# PCI_dos_Motores.net
KiCad netlist of a schematic drawn in EAGLE
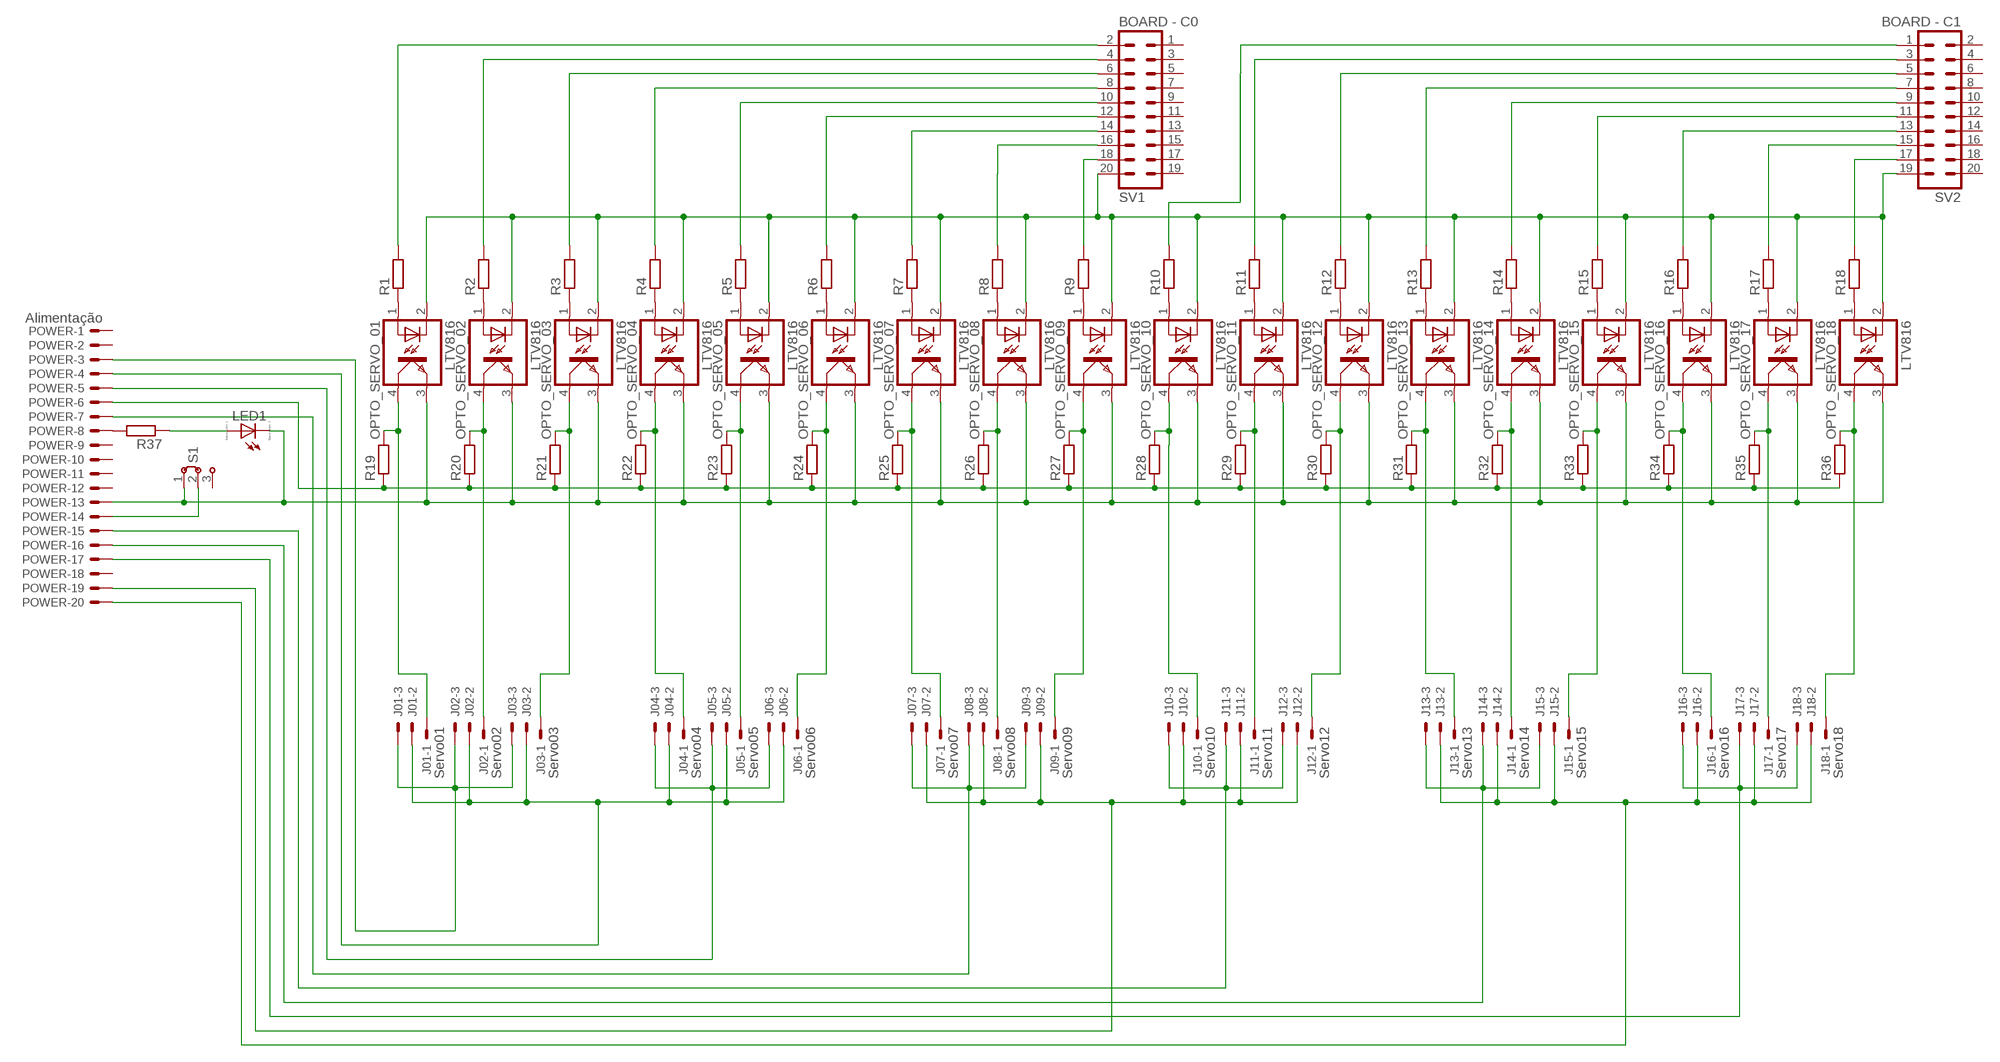
[diagram p0: schematic, sheet 1]

(export (version "E")
  (design (tool "Eeschema 10.0.6"))
  (components
    (comp (ref "J01")
      (value "Servo01")
      (footprint "eagle-import:7395-03")
      (libsource (lib "eagle-import") (part "22-?-0305-7038"))
    )
    (comp (ref "J02")
      (value "Servo02")
      (footprint "eagle-import:7395-03")
      (libsource (lib "eagle-import") (part "22-?-0305-7038"))
    )
    (comp (ref "J03")
      (value "Servo03")
      (footprint "eagle-import:7395-03")
      (libsource (lib "eagle-import") (part "22-?-0305-7038"))
    )
    (comp (ref "J04")
      (value "Servo04")
      (footprint "eagle-import:7395-03")
      (libsource (lib "eagle-import") (part "22-?-0305-7038"))
    )
    (comp (ref "J05")
      (value "Servo05")
      (footprint "eagle-import:7395-03")
      (libsource (lib "eagle-import") (part "22-?-0305-7038"))
    )
    (comp (ref "J06")
      (value "Servo06")
      (footprint "eagle-import:7395-03")
      (libsource (lib "eagle-import") (part "22-?-0305-7038"))
    )
    (comp (ref "J07")
      (value "Servo07")
      (footprint "eagle-import:7395-03")
      (libsource (lib "eagle-import") (part "22-?-0305-7038"))
    )
    (comp (ref "J08")
      (value "Servo08")
      (footprint "eagle-import:7395-03")
      (libsource (lib "eagle-import") (part "22-?-0305-7038"))
    )
    (comp (ref "J09")
      (value "Servo09")
      (footprint "eagle-import:7395-03")
      (libsource (lib "eagle-import") (part "22-?-0305-7038"))
    )
    (comp (ref "J10")
      (value "Servo10")
      (footprint "eagle-import:7395-03")
      (libsource (lib "eagle-import") (part "22-?-0305-7038"))
    )
    (comp (ref "J11")
      (value "Servo11")
      (footprint "eagle-import:7395-03")
      (libsource (lib "eagle-import") (part "22-?-0305-7038"))
    )
    (comp (ref "J12")
      (value "Servo12")
      (footprint "eagle-import:7395-03")
      (libsource (lib "eagle-import") (part "22-?-0305-7038"))
    )
    (comp (ref "J13")
      (value "Servo13")
      (footprint "eagle-import:7395-03")
      (libsource (lib "eagle-import") (part "22-?-0305-7038"))
    )
    (comp (ref "J14")
      (value "Servo14")
      (footprint "eagle-import:7395-03")
      (libsource (lib "eagle-import") (part "22-?-0305-7038"))
    )
    (comp (ref "J15")
      (value "Servo15")
      (footprint "eagle-import:7395-03")
      (libsource (lib "eagle-import") (part "22-?-0305-7038"))
    )
    (comp (ref "J16")
      (value "Servo16")
      (footprint "eagle-import:7395-03")
      (libsource (lib "eagle-import") (part "22-?-0305-7038"))
    )
    (comp (ref "J17")
      (value "Servo17")
      (footprint "eagle-import:7395-03")
      (libsource (lib "eagle-import") (part "22-?-0305-7038"))
    )
    (comp (ref "J18")
      (value "Servo18")
      (footprint "eagle-import:7395-03")
      (libsource (lib "eagle-import") (part "22-?-0305-7038"))
    )
    (comp (ref "LED1")
      (value "LED_ELD260")
      (footprint "eagle-import:LED_LD260")
      (libsource (lib "eagle-import") (part "LED_ELD260"))
    )
    (comp (ref "OPTO_SERVO_01")
      (value "LTV816")
      (footprint "eagle-import:DIL04")
      (libsource (lib "eagle-import") (part "LTV816"))
    )
    (comp (ref "OPTO_SERVO_02")
      (value "LTV816")
      (footprint "eagle-import:DIL04")
      (libsource (lib "eagle-import") (part "LTV816"))
    )
    (comp (ref "OPTO_SERVO_03")
      (value "LTV816")
      (footprint "eagle-import:DIL04")
      (libsource (lib "eagle-import") (part "LTV816"))
    )
    (comp (ref "OPTO_SERVO_04")
      (value "LTV816")
      (footprint "eagle-import:DIL04")
      (libsource (lib "eagle-import") (part "LTV816"))
    )
    (comp (ref "OPTO_SERVO_05")
      (value "LTV816")
      (footprint "eagle-import:DIL04")
      (libsource (lib "eagle-import") (part "LTV816"))
    )
    (comp (ref "OPTO_SERVO_06")
      (value "LTV816")
      (footprint "eagle-import:DIL04")
      (libsource (lib "eagle-import") (part "LTV816"))
    )
    (comp (ref "OPTO_SERVO_07")
      (value "LTV816")
      (footprint "eagle-import:DIL04")
      (libsource (lib "eagle-import") (part "LTV816"))
    )
    (comp (ref "OPTO_SERVO_08")
      (value "LTV816")
      (footprint "eagle-import:DIL04")
      (libsource (lib "eagle-import") (part "LTV816"))
    )
    (comp (ref "OPTO_SERVO_09")
      (value "LTV816")
      (footprint "eagle-import:DIL04")
      (libsource (lib "eagle-import") (part "LTV816"))
    )
    (comp (ref "OPTO_SERVO_10")
      (value "LTV816")
      (footprint "eagle-import:DIL04")
      (libsource (lib "eagle-import") (part "LTV816"))
    )
    (comp (ref "OPTO_SERVO_11")
      (value "LTV816")
      (footprint "eagle-import:DIL04")
      (libsource (lib "eagle-import") (part "LTV816"))
    )
    (comp (ref "OPTO_SERVO_12")
      (value "LTV816")
      (footprint "eagle-import:DIL04")
      (libsource (lib "eagle-import") (part "LTV816"))
    )
    (comp (ref "OPTO_SERVO_13")
      (value "LTV816")
      (footprint "eagle-import:DIL04")
      (libsource (lib "eagle-import") (part "LTV816"))
    )
    (comp (ref "OPTO_SERVO_14")
      (value "LTV816")
      (footprint "eagle-import:DIL04")
      (libsource (lib "eagle-import") (part "LTV816"))
    )
    (comp (ref "OPTO_SERVO_15")
      (value "LTV816")
      (footprint "eagle-import:DIL04")
      (libsource (lib "eagle-import") (part "LTV816"))
    )
    (comp (ref "OPTO_SERVO_16")
      (value "LTV816")
      (footprint "eagle-import:DIL04")
      (libsource (lib "eagle-import") (part "LTV816"))
    )
    (comp (ref "OPTO_SERVO_17")
      (value "LTV816")
      (footprint "eagle-import:DIL04")
      (libsource (lib "eagle-import") (part "LTV816"))
    )
    (comp (ref "OPTO_SERVO_18")
      (value "LTV816")
      (footprint "eagle-import:DIL04")
      (libsource (lib "eagle-import") (part "LTV816"))
    )
    (comp (ref "POWER")
      (value "Alimentação")
      (footprint "eagle-import:5566-20")
      (libsource (lib "eagle-import") (part "5566-20"))
    )
    (comp (ref "R1")
      (value "R-EU_0309/10")
      (footprint "eagle-import:0309_10")
      (libsource (lib "eagle-import") (part "R-EU_0309/10"))
    )
    (comp (ref "R2")
      (value "R-EU_0309/10")
      (footprint "eagle-import:0309_10")
      (libsource (lib "eagle-import") (part "R-EU_0309/10"))
    )
    (comp (ref "R3")
      (value "R-EU_0309/10")
      (footprint "eagle-import:0309_10")
      (libsource (lib "eagle-import") (part "R-EU_0309/10"))
    )
    (comp (ref "R4")
      (value "R-EU_0309/10")
      (footprint "eagle-import:0309_10")
      (libsource (lib "eagle-import") (part "R-EU_0309/10"))
    )
    (comp (ref "R5")
      (value "R-EU_0309/10")
      (footprint "eagle-import:0309_10")
      (libsource (lib "eagle-import") (part "R-EU_0309/10"))
    )
    (comp (ref "R6")
      (value "R-EU_0309/10")
      (footprint "eagle-import:0309_10")
      (libsource (lib "eagle-import") (part "R-EU_0309/10"))
    )
    (comp (ref "R7")
      (value "R-EU_0309/10")
      (footprint "eagle-import:0309_10")
      (libsource (lib "eagle-import") (part "R-EU_0309/10"))
    )
    (comp (ref "R8")
      (value "R-EU_0309/10")
      (footprint "eagle-import:0309_10")
      (libsource (lib "eagle-import") (part "R-EU_0309/10"))
    )
    (comp (ref "R9")
      (value "R-EU_0309/10")
      (footprint "eagle-import:0309_10")
      (libsource (lib "eagle-import") (part "R-EU_0309/10"))
    )
    (comp (ref "R10")
      (value "R-EU_0309/10")
      (footprint "eagle-import:0309_10")
      (libsource (lib "eagle-import") (part "R-EU_0309/10"))
    )
    (comp (ref "R11")
      (value "R-EU_0309/10")
      (footprint "eagle-import:0309_10")
      (libsource (lib "eagle-import") (part "R-EU_0309/10"))
    )
    (comp (ref "R12")
      (value "R-EU_0309/10")
      (footprint "eagle-import:0309_10")
      (libsource (lib "eagle-import") (part "R-EU_0309/10"))
    )
    (comp (ref "R13")
      (value "R-EU_0309/10")
      (footprint "eagle-import:0309_10")
      (libsource (lib "eagle-import") (part "R-EU_0309/10"))
    )
    (comp (ref "R14")
      (value "R-EU_0309/10")
      (footprint "eagle-import:0309_10")
      (libsource (lib "eagle-import") (part "R-EU_0309/10"))
    )
    (comp (ref "R15")
      (value "R-EU_0309/10")
      (footprint "eagle-import:0309_10")
      (libsource (lib "eagle-import") (part "R-EU_0309/10"))
    )
    (comp (ref "R16")
      (value "R-EU_0309/10")
      (footprint "eagle-import:0309_10")
      (libsource (lib "eagle-import") (part "R-EU_0309/10"))
    )
    (comp (ref "R17")
      (value "R-EU_0309/10")
      (footprint "eagle-import:0309_10")
      (libsource (lib "eagle-import") (part "R-EU_0309/10"))
    )
    (comp (ref "R18")
      (value "R-EU_0309/10")
      (footprint "eagle-import:0309_10")
      (libsource (lib "eagle-import") (part "R-EU_0309/10"))
    )
    (comp (ref "R19")
      (value "R-EU_0309/10")
      (footprint "eagle-import:0309_10")
      (libsource (lib "eagle-import") (part "R-EU_0309/10"))
    )
    (comp (ref "R20")
      (value "R-EU_0309/10")
      (footprint "eagle-import:0309_10")
      (libsource (lib "eagle-import") (part "R-EU_0309/10"))
    )
    (comp (ref "R21")
      (value "R-EU_0309/10")
      (footprint "eagle-import:0309_10")
      (libsource (lib "eagle-import") (part "R-EU_0309/10"))
    )
    (comp (ref "R22")
      (value "R-EU_0309/10")
      (footprint "eagle-import:0309_10")
      (libsource (lib "eagle-import") (part "R-EU_0309/10"))
    )
    (comp (ref "R23")
      (value "R-EU_0309/10")
      (footprint "eagle-import:0309_10")
      (libsource (lib "eagle-import") (part "R-EU_0309/10"))
    )
    (comp (ref "R24")
      (value "R-EU_0309/10")
      (footprint "eagle-import:0309_10")
      (libsource (lib "eagle-import") (part "R-EU_0309/10"))
    )
    (comp (ref "R25")
      (value "R-EU_0309/10")
      (footprint "eagle-import:0309_10")
      (libsource (lib "eagle-import") (part "R-EU_0309/10"))
    )
    (comp (ref "R26")
      (value "R-EU_0309/10")
      (footprint "eagle-import:0309_10")
      (libsource (lib "eagle-import") (part "R-EU_0309/10"))
    )
    (comp (ref "R27")
      (value "R-EU_0309/10")
      (footprint "eagle-import:0309_10")
      (libsource (lib "eagle-import") (part "R-EU_0309/10"))
    )
    (comp (ref "R28")
      (value "R-EU_0309/10")
      (footprint "eagle-import:0309_10")
      (libsource (lib "eagle-import") (part "R-EU_0309/10"))
    )
    (comp (ref "R29")
      (value "R-EU_0309/10")
      (footprint "eagle-import:0309_10")
      (libsource (lib "eagle-import") (part "R-EU_0309/10"))
    )
    (comp (ref "R30")
      (value "R-EU_0309/10")
      (footprint "eagle-import:0309_10")
      (libsource (lib "eagle-import") (part "R-EU_0309/10"))
    )
    (comp (ref "R31")
      (value "R-EU_0309/10")
      (footprint "eagle-import:0309_10")
      (libsource (lib "eagle-import") (part "R-EU_0309/10"))
    )
    (comp (ref "R32")
      (value "R-EU_0309/10")
      (footprint "eagle-import:0309_10")
      (libsource (lib "eagle-import") (part "R-EU_0309/10"))
    )
    (comp (ref "R33")
      (value "R-EU_0309/10")
      (footprint "eagle-import:0309_10")
      (libsource (lib "eagle-import") (part "R-EU_0309/10"))
    )
    (comp (ref "R34")
      (value "R-EU_0309/10")
      (footprint "eagle-import:0309_10")
      (libsource (lib "eagle-import") (part "R-EU_0309/10"))
    )
    (comp (ref "R35")
      (value "R-EU_0309/10")
      (footprint "eagle-import:0309_10")
      (libsource (lib "eagle-import") (part "R-EU_0309/10"))
    )
    (comp (ref "R36")
      (value "R-EU_0309/10")
      (footprint "eagle-import:0309_10")
      (libsource (lib "eagle-import") (part "R-EU_0309/10"))
    )
    (comp (ref "R37")
      (value "R-EU_0309/10")
      (footprint "eagle-import:0309_10")
      (libsource (lib "eagle-import") (part "R-EU_0309/10"))
    )
    (comp (ref "S1")
      (value "J2X2MM")
      (footprint "eagle-import:04C")
      (libsource (lib "eagle-import") (part "J2X2MM"))
    )
    (comp (ref "SV1")
      (value "BOARD - C0")
      (footprint "eagle-import:ML20")
      (libsource (lib "eagle-import") (part "ML20"))
    )
    (comp (ref "SV2")
      (value "BOARD - C1")
      (footprint "eagle-import:ML20")
      (libsource (lib "eagle-import") (part "ML20"))
    )
  )
  (nets
    (net (code "1") (name "Net-(J01A-S)") (class "Default")
      (node (ref "J01") (pin "1") (pinfunction "S_1") (pintype "passive"))
      (node (ref "OPTO_SERVO_01") (pin "4") (pinfunction "COL_4") (pintype "passive"))
      (node (ref "R19") (pin "2") (pinfunction "2_2") (pintype "passive"))
    )
    (net (code "2") (name "Net-(J01B-S)") (class "Default")
      (node (ref "J01") (pin "2") (pinfunction "S_2") (pintype "passive"))
      (node (ref "J02") (pin "2") (pinfunction "S_2") (pintype "passive"))
      (node (ref "J03") (pin "2") (pinfunction "S_2") (pintype "passive"))
      (node (ref "J04") (pin "2") (pinfunction "S_2") (pintype "passive"))
      (node (ref "J05") (pin "2") (pinfunction "S_2") (pintype "passive"))
      (node (ref "J06") (pin "2") (pinfunction "S_2") (pintype "passive"))
      (node (ref "POWER") (pin "4") (pinfunction "S_4") (pintype "passive"))
    )
    (net (code "3") (name "Net-(J01C-S)") (class "Default")
      (node (ref "J01") (pin "3") (pinfunction "S_3") (pintype "passive"))
      (node (ref "J02") (pin "3") (pinfunction "S_3") (pintype "passive"))
      (node (ref "J03") (pin "3") (pinfunction "S_3") (pintype "passive"))
      (node (ref "POWER") (pin "3") (pinfunction "S_3") (pintype "passive"))
    )
    (net (code "4") (name "Net-(J02A-S)") (class "Default")
      (node (ref "J02") (pin "1") (pinfunction "S_1") (pintype "passive"))
      (node (ref "OPTO_SERVO_02") (pin "4") (pinfunction "COL_4") (pintype "passive"))
      (node (ref "R20") (pin "2") (pinfunction "2_2") (pintype "passive"))
    )
    (net (code "5") (name "Net-(J03A-S)") (class "Default")
      (node (ref "J03") (pin "1") (pinfunction "S_1") (pintype "passive"))
      (node (ref "OPTO_SERVO_03") (pin "4") (pinfunction "COL_4") (pintype "passive"))
      (node (ref "R21") (pin "2") (pinfunction "2_2") (pintype "passive"))
    )
    (net (code "6") (name "Net-(J04A-S)") (class "Default")
      (node (ref "J04") (pin "1") (pinfunction "S_1") (pintype "passive"))
      (node (ref "OPTO_SERVO_04") (pin "4") (pinfunction "COL_4") (pintype "passive"))
      (node (ref "R22") (pin "2") (pinfunction "2_2") (pintype "passive"))
    )
    (net (code "7") (name "Net-(J04C-S)") (class "Default")
      (node (ref "J04") (pin "3") (pinfunction "S_3") (pintype "passive"))
      (node (ref "J05") (pin "3") (pinfunction "S_3") (pintype "passive"))
      (node (ref "J06") (pin "3") (pinfunction "S_3") (pintype "passive"))
      (node (ref "POWER") (pin "5") (pinfunction "S_5") (pintype "passive"))
    )
    (net (code "8") (name "Net-(J05A-S)") (class "Default")
      (node (ref "J05") (pin "1") (pinfunction "S_1") (pintype "passive"))
      (node (ref "OPTO_SERVO_05") (pin "4") (pinfunction "COL_4") (pintype "passive"))
      (node (ref "R23") (pin "2") (pinfunction "2_2") (pintype "passive"))
    )
    (net (code "9") (name "Net-(J06A-S)") (class "Default")
      (node (ref "J06") (pin "1") (pinfunction "S_1") (pintype "passive"))
      (node (ref "OPTO_SERVO_06") (pin "4") (pinfunction "COL_4") (pintype "passive"))
      (node (ref "R24") (pin "2") (pinfunction "2_2") (pintype "passive"))
    )
    (net (code "10") (name "Net-(J07A-S)") (class "Default")
      (node (ref "J07") (pin "1") (pinfunction "S_1") (pintype "passive"))
      (node (ref "OPTO_SERVO_07") (pin "4") (pinfunction "COL_4") (pintype "passive"))
      (node (ref "R25") (pin "2") (pinfunction "2_2") (pintype "passive"))
    )
    (net (code "11") (name "Net-(J07B-S)") (class "Default")
      (node (ref "J07") (pin "2") (pinfunction "S_2") (pintype "passive"))
      (node (ref "J08") (pin "2") (pinfunction "S_2") (pintype "passive"))
      (node (ref "J09") (pin "2") (pinfunction "S_2") (pintype "passive"))
      (node (ref "J10") (pin "2") (pinfunction "S_2") (pintype "passive"))
      (node (ref "J11") (pin "2") (pinfunction "S_2") (pintype "passive"))
      (node (ref "J12") (pin "2") (pinfunction "S_2") (pintype "passive"))
      (node (ref "POWER") (pin "19") (pinfunction "S_19") (pintype "passive"))
    )
    (net (code "12") (name "Net-(J07C-S)") (class "Default")
      (node (ref "J07") (pin "3") (pinfunction "S_3") (pintype "passive"))
      (node (ref "J08") (pin "3") (pinfunction "S_3") (pintype "passive"))
      (node (ref "J09") (pin "3") (pinfunction "S_3") (pintype "passive"))
      (node (ref "POWER") (pin "7") (pinfunction "S_7") (pintype "passive"))
    )
    (net (code "13") (name "Net-(J08A-S)") (class "Default")
      (node (ref "J08") (pin "1") (pinfunction "S_1") (pintype "passive"))
      (node (ref "OPTO_SERVO_08") (pin "4") (pinfunction "COL_4") (pintype "passive"))
      (node (ref "R26") (pin "2") (pinfunction "2_2") (pintype "passive"))
    )
    (net (code "14") (name "Net-(J09A-S)") (class "Default")
      (node (ref "J09") (pin "1") (pinfunction "S_1") (pintype "passive"))
      (node (ref "OPTO_SERVO_09") (pin "4") (pinfunction "COL_4") (pintype "passive"))
      (node (ref "R27") (pin "2") (pinfunction "2_2") (pintype "passive"))
    )
    (net (code "15") (name "Net-(J10A-S)") (class "Default")
      (node (ref "J10") (pin "1") (pinfunction "S_1") (pintype "passive"))
      (node (ref "OPTO_SERVO_10") (pin "4") (pinfunction "COL_4") (pintype "passive"))
      (node (ref "R28") (pin "2") (pinfunction "2_2") (pintype "passive"))
    )
    (net (code "16") (name "Net-(J10C-S)") (class "Default")
      (node (ref "J10") (pin "3") (pinfunction "S_3") (pintype "passive"))
      (node (ref "J11") (pin "3") (pinfunction "S_3") (pintype "passive"))
      (node (ref "J12") (pin "3") (pinfunction "S_3") (pintype "passive"))
      (node (ref "POWER") (pin "15") (pinfunction "S_15") (pintype "passive"))
    )
    (net (code "17") (name "Net-(J11A-S)") (class "Default")
      (node (ref "J11") (pin "1") (pinfunction "S_1") (pintype "passive"))
      (node (ref "OPTO_SERVO_11") (pin "4") (pinfunction "COL_4") (pintype "passive"))
      (node (ref "R29") (pin "2") (pinfunction "2_2") (pintype "passive"))
    )
    (net (code "18") (name "Net-(J12A-S)") (class "Default")
      (node (ref "J12") (pin "1") (pinfunction "S_1") (pintype "passive"))
      (node (ref "OPTO_SERVO_12") (pin "4") (pinfunction "COL_4") (pintype "passive"))
      (node (ref "R30") (pin "2") (pinfunction "2_2") (pintype "passive"))
    )
    (net (code "19") (name "Net-(J13A-S)") (class "Default")
      (node (ref "J13") (pin "1") (pinfunction "S_1") (pintype "passive"))
      (node (ref "OPTO_SERVO_13") (pin "4") (pinfunction "COL_4") (pintype "passive"))
      (node (ref "R31") (pin "2") (pinfunction "2_2") (pintype "passive"))
    )
    (net (code "20") (name "Net-(J13B-S)") (class "Default")
      (node (ref "J13") (pin "2") (pinfunction "S_2") (pintype "passive"))
      (node (ref "J14") (pin "2") (pinfunction "S_2") (pintype "passive"))
      (node (ref "J15") (pin "2") (pinfunction "S_2") (pintype "passive"))
      (node (ref "J16") (pin "2") (pinfunction "S_2") (pintype "passive"))
      (node (ref "J17") (pin "2") (pinfunction "S_2") (pintype "passive"))
      (node (ref "J18") (pin "2") (pinfunction "S_2") (pintype "passive"))
      (node (ref "POWER") (pin "20") (pinfunction "S_20") (pintype "passive"))
    )
    (net (code "21") (name "Net-(J13C-S)") (class "Default")
      (node (ref "J13") (pin "3") (pinfunction "S_3") (pintype "passive"))
      (node (ref "J14") (pin "3") (pinfunction "S_3") (pintype "passive"))
      (node (ref "J15") (pin "3") (pinfunction "S_3") (pintype "passive"))
      (node (ref "POWER") (pin "16") (pinfunction "S_16") (pintype "passive"))
    )
    (net (code "22") (name "Net-(J14A-S)") (class "Default")
      (node (ref "J14") (pin "1") (pinfunction "S_1") (pintype "passive"))
      (node (ref "OPTO_SERVO_14") (pin "4") (pinfunction "COL_4") (pintype "passive"))
      (node (ref "R32") (pin "2") (pinfunction "2_2") (pintype "passive"))
    )
    (net (code "23") (name "Net-(J15A-S)") (class "Default")
      (node (ref "J15") (pin "1") (pinfunction "S_1") (pintype "passive"))
      (node (ref "OPTO_SERVO_15") (pin "4") (pinfunction "COL_4") (pintype "passive"))
      (node (ref "R33") (pin "2") (pinfunction "2_2") (pintype "passive"))
    )
    (net (code "24") (name "Net-(J16A-S)") (class "Default")
      (node (ref "J16") (pin "1") (pinfunction "S_1") (pintype "passive"))
      (node (ref "OPTO_SERVO_16") (pin "4") (pinfunction "COL_4") (pintype "passive"))
      (node (ref "R34") (pin "2") (pinfunction "2_2") (pintype "passive"))
    )
    (net (code "25") (name "Net-(J16C-S)") (class "Default")
      (node (ref "J16") (pin "3") (pinfunction "S_3") (pintype "passive"))
      (node (ref "J17") (pin "3") (pinfunction "S_3") (pintype "passive"))
      (node (ref "J18") (pin "3") (pinfunction "S_3") (pintype "passive"))
      (node (ref "POWER") (pin "17") (pinfunction "S_17") (pintype "passive"))
    )
    (net (code "26") (name "Net-(J17A-S)") (class "Default")
      (node (ref "J17") (pin "1") (pinfunction "S_1") (pintype "passive"))
      (node (ref "OPTO_SERVO_17") (pin "4") (pinfunction "COL_4") (pintype "passive"))
      (node (ref "R35") (pin "2") (pinfunction "2_2") (pintype "passive"))
    )
    (net (code "27") (name "Net-(J18A-S)") (class "Default")
      (node (ref "J18") (pin "1") (pinfunction "S_1") (pintype "passive"))
      (node (ref "OPTO_SERVO_18") (pin "4") (pinfunction "COL_4") (pintype "passive"))
      (node (ref "R36") (pin "2") (pinfunction "2_2") (pintype "passive"))
    )
    (net (code "28") (name "Net-(LED1-C)") (class "Default")
      (node (ref "LED1") (pin "K") (pinfunction "C_K") (pintype "passive"))
      (node (ref "OPTO_SERVO_01") (pin "3") (pinfunction "EMIT_3") (pintype "passive"))
      (node (ref "OPTO_SERVO_02") (pin "3") (pinfunction "EMIT_3") (pintype "passive"))
      (node (ref "OPTO_SERVO_03") (pin "3") (pinfunction "EMIT_3") (pintype "passive"))
      (node (ref "OPTO_SERVO_04") (pin "3") (pinfunction "EMIT_3") (pintype "passive"))
      (node (ref "OPTO_SERVO_05") (pin "3") (pinfunction "EMIT_3") (pintype "passive"))
      (node (ref "OPTO_SERVO_06") (pin "3") (pinfunction "EMIT_3") (pintype "passive"))
      (node (ref "OPTO_SERVO_07") (pin "3") (pinfunction "EMIT_3") (pintype "passive"))
      (node (ref "OPTO_SERVO_08") (pin "3") (pinfunction "EMIT_3") (pintype "passive"))
      (node (ref "OPTO_SERVO_09") (pin "3") (pinfunction "EMIT_3") (pintype "passive"))
      (node (ref "OPTO_SERVO_10") (pin "3") (pinfunction "EMIT_3") (pintype "passive"))
      (node (ref "OPTO_SERVO_11") (pin "3") (pinfunction "EMIT_3") (pintype "passive"))
      (node (ref "OPTO_SERVO_12") (pin "3") (pinfunction "EMIT_3") (pintype "passive"))
      (node (ref "OPTO_SERVO_13") (pin "3") (pinfunction "EMIT_3") (pintype "passive"))
      (node (ref "OPTO_SERVO_14") (pin "3") (pinfunction "EMIT_3") (pintype "passive"))
      (node (ref "OPTO_SERVO_15") (pin "3") (pinfunction "EMIT_3") (pintype "passive"))
      (node (ref "OPTO_SERVO_16") (pin "3") (pinfunction "EMIT_3") (pintype "passive"))
      (node (ref "OPTO_SERVO_17") (pin "3") (pinfunction "EMIT_3") (pintype "passive"))
      (node (ref "OPTO_SERVO_18") (pin "3") (pinfunction "EMIT_3") (pintype "passive"))
      (node (ref "POWER") (pin "13") (pinfunction "S_13") (pintype "passive"))
      (node (ref "S1") (pin "1") (pinfunction "1_1") (pintype "passive"))
    )
    (net (code "29") (name "Net-(LED1-PadA)") (class "Default")
      (node (ref "LED1") (pin "A") (pinfunction "A_A") (pintype "passive"))
      (node (ref "R37") (pin "1") (pinfunction "1_1") (pintype "passive"))
    )
    (net (code "30") (name "Net-(OPTO_SERVO_01-A)") (class "Default")
      (node (ref "OPTO_SERVO_01") (pin "1") (pinfunction "A_1") (pintype "passive"))
      (node (ref "R1") (pin "1") (pinfunction "1_1") (pintype "passive"))
    )
    (net (code "31") (name "Net-(OPTO_SERVO_01-C)") (class "Default")
      (node (ref "OPTO_SERVO_01") (pin "2") (pinfunction "C_2") (pintype "passive"))
      (node (ref "OPTO_SERVO_02") (pin "2") (pinfunction "C_2") (pintype "passive"))
      (node (ref "OPTO_SERVO_03") (pin "2") (pinfunction "C_2") (pintype "passive"))
      (node (ref "OPTO_SERVO_04") (pin "2") (pinfunction "C_2") (pintype "passive"))
      (node (ref "OPTO_SERVO_05") (pin "2") (pinfunction "C_2") (pintype "passive"))
      (node (ref "OPTO_SERVO_06") (pin "2") (pinfunction "C_2") (pintype "passive"))
      (node (ref "OPTO_SERVO_07") (pin "2") (pinfunction "C_2") (pintype "passive"))
      (node (ref "OPTO_SERVO_08") (pin "2") (pinfunction "C_2") (pintype "passive"))
      (node (ref "OPTO_SERVO_09") (pin "2") (pinfunction "C_2") (pintype "passive"))
      (node (ref "OPTO_SERVO_10") (pin "2") (pinfunction "C_2") (pintype "passive"))
      (node (ref "OPTO_SERVO_11") (pin "2") (pinfunction "C_2") (pintype "passive"))
      (node (ref "OPTO_SERVO_12") (pin "2") (pinfunction "C_2") (pintype "passive"))
      (node (ref "OPTO_SERVO_13") (pin "2") (pinfunction "C_2") (pintype "passive"))
      (node (ref "OPTO_SERVO_14") (pin "2") (pinfunction "C_2") (pintype "passive"))
      (node (ref "OPTO_SERVO_15") (pin "2") (pinfunction "C_2") (pintype "passive"))
      (node (ref "OPTO_SERVO_16") (pin "2") (pinfunction "C_2") (pintype "passive"))
      (node (ref "OPTO_SERVO_17") (pin "2") (pinfunction "C_2") (pintype "passive"))
      (node (ref "OPTO_SERVO_18") (pin "2") (pinfunction "C_2") (pintype "passive"))
      (node (ref "SV1") (pin "20") (pinfunction "20_20") (pintype "passive"))
      (node (ref "SV2") (pin "19") (pinfunction "19_19") (pintype "passive"))
    )
    (net (code "32") (name "Net-(OPTO_SERVO_02-A)") (class "Default")
      (node (ref "OPTO_SERVO_02") (pin "1") (pinfunction "A_1") (pintype "passive"))
      (node (ref "R2") (pin "1") (pinfunction "1_1") (pintype "passive"))
    )
    (net (code "33") (name "Net-(OPTO_SERVO_03-A)") (class "Default")
      (node (ref "OPTO_SERVO_03") (pin "1") (pinfunction "A_1") (pintype "passive"))
      (node (ref "R3") (pin "1") (pinfunction "1_1") (pintype "passive"))
    )
    (net (code "34") (name "Net-(OPTO_SERVO_04-A)") (class "Default")
      (node (ref "OPTO_SERVO_04") (pin "1") (pinfunction "A_1") (pintype "passive"))
      (node (ref "R4") (pin "1") (pinfunction "1_1") (pintype "passive"))
    )
    (net (code "35") (name "Net-(OPTO_SERVO_05-A)") (class "Default")
      (node (ref "OPTO_SERVO_05") (pin "1") (pinfunction "A_1") (pintype "passive"))
      (node (ref "R5") (pin "1") (pinfunction "1_1") (pintype "passive"))
    )
    (net (code "36") (name "Net-(OPTO_SERVO_06-A)") (class "Default")
      (node (ref "OPTO_SERVO_06") (pin "1") (pinfunction "A_1") (pintype "passive"))
      (node (ref "R6") (pin "1") (pinfunction "1_1") (pintype "passive"))
    )
    (net (code "37") (name "Net-(OPTO_SERVO_07-A)") (class "Default")
      (node (ref "OPTO_SERVO_07") (pin "1") (pinfunction "A_1") (pintype "passive"))
      (node (ref "R7") (pin "1") (pinfunction "1_1") (pintype "passive"))
    )
    (net (code "38") (name "Net-(OPTO_SERVO_08-A)") (class "Default")
      (node (ref "OPTO_SERVO_08") (pin "1") (pinfunction "A_1") (pintype "passive"))
      (node (ref "R8") (pin "1") (pinfunction "1_1") (pintype "passive"))
    )
    (net (code "39") (name "Net-(OPTO_SERVO_09-A)") (class "Default")
      (node (ref "OPTO_SERVO_09") (pin "1") (pinfunction "A_1") (pintype "passive"))
      (node (ref "R9") (pin "1") (pinfunction "1_1") (pintype "passive"))
    )
    (net (code "40") (name "Net-(OPTO_SERVO_10-A)") (class "Default")
      (node (ref "OPTO_SERVO_10") (pin "1") (pinfunction "A_1") (pintype "passive"))
      (node (ref "R10") (pin "1") (pinfunction "1_1") (pintype "passive"))
    )
    (net (code "41") (name "Net-(OPTO_SERVO_11-A)") (class "Default")
      (node (ref "OPTO_SERVO_11") (pin "1") (pinfunction "A_1") (pintype "passive"))
      (node (ref "R11") (pin "1") (pinfunction "1_1") (pintype "passive"))
    )
    (net (code "42") (name "Net-(OPTO_SERVO_12-A)") (class "Default")
      (node (ref "OPTO_SERVO_12") (pin "1") (pinfunction "A_1") (pintype "passive"))
      (node (ref "R12") (pin "1") (pinfunction "1_1") (pintype "passive"))
    )
    (net (code "43") (name "Net-(OPTO_SERVO_13-A)") (class "Default")
      (node (ref "OPTO_SERVO_13") (pin "1") (pinfunction "A_1") (pintype "passive"))
      (node (ref "R13") (pin "1") (pinfunction "1_1") (pintype "passive"))
    )
    (net (code "44") (name "Net-(OPTO_SERVO_14-A)") (class "Default")
      (node (ref "OPTO_SERVO_14") (pin "1") (pinfunction "A_1") (pintype "passive"))
      (node (ref "R14") (pin "1") (pinfunction "1_1") (pintype "passive"))
    )
    (net (code "45") (name "Net-(OPTO_SERVO_15-A)") (class "Default")
      (node (ref "OPTO_SERVO_15") (pin "1") (pinfunction "A_1") (pintype "passive"))
      (node (ref "R15") (pin "1") (pinfunction "1_1") (pintype "passive"))
    )
    (net (code "46") (name "Net-(OPTO_SERVO_16-A)") (class "Default")
      (node (ref "OPTO_SERVO_16") (pin "1") (pinfunction "A_1") (pintype "passive"))
      (node (ref "R16") (pin "1") (pinfunction "1_1") (pintype "passive"))
    )
    (net (code "47") (name "Net-(OPTO_SERVO_17-A)") (class "Default")
      (node (ref "OPTO_SERVO_17") (pin "1") (pinfunction "A_1") (pintype "passive"))
      (node (ref "R17") (pin "1") (pinfunction "1_1") (pintype "passive"))
    )
    (net (code "48") (name "Net-(OPTO_SERVO_18-A)") (class "Default")
      (node (ref "OPTO_SERVO_18") (pin "1") (pinfunction "A_1") (pintype "passive"))
      (node (ref "R18") (pin "1") (pinfunction "1_1") (pintype "passive"))
    )
    (net (code "49") (name "Net-(POWERF-S)") (class "Default")
      (node (ref "POWER") (pin "14") (pinfunction "S_14") (pintype "passive"))
      (node (ref "S1") (pin "2") (pinfunction "2_2") (pintype "passive"))
    )
    (net (code "50") (name "Net-(POWERQ-S)") (class "Default")
      (node (ref "POWER") (pin "6") (pinfunction "S_6") (pintype "passive"))
      (node (ref "R19") (pin "1") (pinfunction "1_1") (pintype "passive"))
      (node (ref "R20") (pin "1") (pinfunction "1_1") (pintype "passive"))
      (node (ref "R21") (pin "1") (pinfunction "1_1") (pintype "passive"))
      (node (ref "R22") (pin "1") (pinfunction "1_1") (pintype "passive"))
      (node (ref "R23") (pin "1") (pinfunction "1_1") (pintype "passive"))
      (node (ref "R24") (pin "1") (pinfunction "1_1") (pintype "passive"))
      (node (ref "R25") (pin "1") (pinfunction "1_1") (pintype "passive"))
      (node (ref "R26") (pin "1") (pinfunction "1_1") (pintype "passive"))
      (node (ref "R27") (pin "1") (pinfunction "1_1") (pintype "passive"))
      (node (ref "R28") (pin "1") (pinfunction "1_1") (pintype "passive"))
      (node (ref "R29") (pin "1") (pinfunction "1_1") (pintype "passive"))
      (node (ref "R30") (pin "1") (pinfunction "1_1") (pintype "passive"))
      (node (ref "R31") (pin "1") (pinfunction "1_1") (pintype "passive"))
      (node (ref "R32") (pin "1") (pinfunction "1_1") (pintype "passive"))
      (node (ref "R33") (pin "1") (pinfunction "1_1") (pintype "passive"))
      (node (ref "R34") (pin "1") (pinfunction "1_1") (pintype "passive"))
      (node (ref "R35") (pin "1") (pinfunction "1_1") (pintype "passive"))
      (node (ref "R36") (pin "1") (pinfunction "1_1") (pintype "passive"))
    )
    (net (code "51") (name "Net-(POWERS-S)") (class "Default")
      (node (ref "POWER") (pin "8") (pinfunction "S_8") (pintype "passive"))
      (node (ref "R37") (pin "2") (pinfunction "2_2") (pintype "passive"))
    )
    (net (code "52") (name "Net-(R1-Pad2)") (class "Default")
      (node (ref "R1") (pin "2") (pinfunction "2_2") (pintype "passive"))
      (node (ref "SV1") (pin "2") (pinfunction "2_2") (pintype "passive"))
    )
    (net (code "53") (name "Net-(R2-Pad2)") (class "Default")
      (node (ref "R2") (pin "2") (pinfunction "2_2") (pintype "passive"))
      (node (ref "SV1") (pin "4") (pinfunction "4_4") (pintype "passive"))
    )
    (net (code "54") (name "Net-(R3-Pad2)") (class "Default")
      (node (ref "R3") (pin "2") (pinfunction "2_2") (pintype "passive"))
      (node (ref "SV1") (pin "6") (pinfunction "6_6") (pintype "passive"))
    )
    (net (code "55") (name "Net-(R4-Pad2)") (class "Default")
      (node (ref "R4") (pin "2") (pinfunction "2_2") (pintype "passive"))
      (node (ref "SV1") (pin "8") (pinfunction "8_8") (pintype "passive"))
    )
    (net (code "56") (name "Net-(R5-Pad2)") (class "Default")
      (node (ref "R5") (pin "2") (pinfunction "2_2") (pintype "passive"))
      (node (ref "SV1") (pin "10") (pinfunction "10_10") (pintype "passive"))
    )
    (net (code "57") (name "Net-(R6-Pad2)") (class "Default")
      (node (ref "R6") (pin "2") (pinfunction "2_2") (pintype "passive"))
      (node (ref "SV1") (pin "12") (pinfunction "12_12") (pintype "passive"))
    )
    (net (code "58") (name "Net-(R7-Pad2)") (class "Default")
      (node (ref "R7") (pin "2") (pinfunction "2_2") (pintype "passive"))
      (node (ref "SV1") (pin "14") (pinfunction "14_14") (pintype "passive"))
    )
    (net (code "59") (name "Net-(R8-Pad2)") (class "Default")
      (node (ref "R8") (pin "2") (pinfunction "2_2") (pintype "passive"))
      (node (ref "SV1") (pin "16") (pinfunction "16_16") (pintype "passive"))
    )
    (net (code "60") (name "Net-(R9-Pad2)") (class "Default")
      (node (ref "R9") (pin "2") (pinfunction "2_2") (pintype "passive"))
      (node (ref "SV1") (pin "18") (pinfunction "18_18") (pintype "passive"))
    )
    (net (code "61") (name "Net-(R10-Pad2)") (class "Default")
      (node (ref "R10") (pin "2") (pinfunction "2_2") (pintype "passive"))
      (node (ref "SV2") (pin "1") (pinfunction "1_1") (pintype "passive"))
    )
    (net (code "62") (name "Net-(R11-Pad2)") (class "Default")
      (node (ref "R11") (pin "2") (pinfunction "2_2") (pintype "passive"))
      (node (ref "SV2") (pin "3") (pinfunction "3_3") (pintype "passive"))
    )
    (net (code "63") (name "Net-(R12-Pad2)") (class "Default")
      (node (ref "R12") (pin "2") (pinfunction "2_2") (pintype "passive"))
      (node (ref "SV2") (pin "5") (pinfunction "5_5") (pintype "passive"))
    )
    (net (code "64") (name "Net-(R13-Pad2)") (class "Default")
      (node (ref "R13") (pin "2") (pinfunction "2_2") (pintype "passive"))
      (node (ref "SV2") (pin "7") (pinfunction "7_7") (pintype "passive"))
    )
    (net (code "65") (name "Net-(R14-Pad2)") (class "Default")
      (node (ref "R14") (pin "2") (pinfunction "2_2") (pintype "passive"))
      (node (ref "SV2") (pin "9") (pinfunction "9_9") (pintype "passive"))
    )
    (net (code "66") (name "Net-(R15-Pad2)") (class "Default")
      (node (ref "R15") (pin "2") (pinfunction "2_2") (pintype "passive"))
      (node (ref "SV2") (pin "11") (pinfunction "11_11") (pintype "passive"))
    )
    (net (code "67") (name "Net-(R16-Pad2)") (class "Default")
      (node (ref "R16") (pin "2") (pinfunction "2_2") (pintype "passive"))
      (node (ref "SV2") (pin "13") (pinfunction "13_13") (pintype "passive"))
    )
    (net (code "68") (name "Net-(R17-Pad2)") (class "Default")
      (node (ref "R17") (pin "2") (pinfunction "2_2") (pintype "passive"))
      (node (ref "SV2") (pin "15") (pinfunction "15_15") (pintype "passive"))
    )
    (net (code "69") (name "Net-(R18-Pad2)") (class "Default")
      (node (ref "R18") (pin "2") (pinfunction "2_2") (pintype "passive"))
      (node (ref "SV2") (pin "17") (pinfunction "17_17") (pintype "passive"))
    )
    (net (code "70") (name "unconnected-(POWERA-S-Pad1)") (class "Default")
      (node (ref "POWER") (pin "1") (pinfunction "S_1") (pintype "passive"))
    )
    (net (code "71") (name "unconnected-(POWERB-S-Pad10)") (class "Default")
      (node (ref "POWER") (pin "10") (pinfunction "S_10") (pintype "passive"))
    )
    (net (code "72") (name "unconnected-(POWERC-S-Pad11)") (class "Default")
      (node (ref "POWER") (pin "11") (pinfunction "S_11") (pintype "passive"))
    )
    (net (code "73") (name "unconnected-(POWERD-S-Pad12)") (class "Default")
      (node (ref "POWER") (pin "12") (pinfunction "S_12") (pintype "passive"))
    )
    (net (code "74") (name "unconnected-(POWERJ-S-Pad18)") (class "Default")
      (node (ref "POWER") (pin "18") (pinfunction "S_18") (pintype "passive"))
    )
    (net (code "75") (name "unconnected-(POWERL-S-Pad2)") (class "Default")
      (node (ref "POWER") (pin "2") (pinfunction "S_2") (pintype "passive"))
    )
    (net (code "76") (name "unconnected-(POWERT-S-Pad9)") (class "Default")
      (node (ref "POWER") (pin "9") (pinfunction "S_9") (pintype "passive"))
    )
    (net (code "77") (name "unconnected-(S1-Pad3)") (class "Default")
      (node (ref "S1") (pin "3") (pinfunction "3_3") (pintype "passive"))
    )
    (net (code "78") (name "unconnected-(SV1-Pad1)") (class "Default")
      (node (ref "SV1") (pin "1") (pinfunction "1_1") (pintype "passive"))
    )
    (net (code "79") (name "unconnected-(SV1-Pad3)") (class "Default")
      (node (ref "SV1") (pin "3") (pinfunction "3_3") (pintype "passive"))
    )
    (net (code "80") (name "unconnected-(SV1-Pad5)") (class "Default")
      (node (ref "SV1") (pin "5") (pinfunction "5_5") (pintype "passive"))
    )
    (net (code "81") (name "unconnected-(SV1-Pad7)") (class "Default")
      (node (ref "SV1") (pin "7") (pinfunction "7_7") (pintype "passive"))
    )
    (net (code "82") (name "unconnected-(SV1-Pad9)") (class "Default")
      (node (ref "SV1") (pin "9") (pinfunction "9_9") (pintype "passive"))
    )
    (net (code "83") (name "unconnected-(SV1-Pad11)") (class "Default")
      (node (ref "SV1") (pin "11") (pinfunction "11_11") (pintype "passive"))
    )
    (net (code "84") (name "unconnected-(SV1-Pad13)") (class "Default")
      (node (ref "SV1") (pin "13") (pinfunction "13_13") (pintype "passive"))
    )
    (net (code "85") (name "unconnected-(SV1-Pad15)") (class "Default")
      (node (ref "SV1") (pin "15") (pinfunction "15_15") (pintype "passive"))
    )
    (net (code "86") (name "unconnected-(SV1-Pad17)") (class "Default")
      (node (ref "SV1") (pin "17") (pinfunction "17_17") (pintype "passive"))
    )
    (net (code "87") (name "unconnected-(SV1-Pad19)") (class "Default")
      (node (ref "SV1") (pin "19") (pinfunction "19_19") (pintype "passive"))
    )
    (net (code "88") (name "unconnected-(SV2-Pad2)") (class "Default")
      (node (ref "SV2") (pin "2") (pinfunction "2_2") (pintype "passive"))
    )
    (net (code "89") (name "unconnected-(SV2-Pad4)") (class "Default")
      (node (ref "SV2") (pin "4") (pinfunction "4_4") (pintype "passive"))
    )
    (net (code "90") (name "unconnected-(SV2-Pad6)") (class "Default")
      (node (ref "SV2") (pin "6") (pinfunction "6_6") (pintype "passive"))
    )
    (net (code "91") (name "unconnected-(SV2-Pad8)") (class "Default")
      (node (ref "SV2") (pin "8") (pinfunction "8_8") (pintype "passive"))
    )
    (net (code "92") (name "unconnected-(SV2-Pad10)") (class "Default")
      (node (ref "SV2") (pin "10") (pinfunction "10_10") (pintype "passive"))
    )
    (net (code "93") (name "unconnected-(SV2-Pad12)") (class "Default")
      (node (ref "SV2") (pin "12") (pinfunction "12_12") (pintype "passive"))
    )
    (net (code "94") (name "unconnected-(SV2-Pad14)") (class "Default")
      (node (ref "SV2") (pin "14") (pinfunction "14_14") (pintype "passive"))
    )
    (net (code "95") (name "unconnected-(SV2-Pad16)") (class "Default")
      (node (ref "SV2") (pin "16") (pinfunction "16_16") (pintype "passive"))
    )
    (net (code "96") (name "unconnected-(SV2-Pad18)") (class "Default")
      (node (ref "SV2") (pin "18") (pinfunction "18_18") (pintype "passive"))
    )
    (net (code "97") (name "unconnected-(SV2-Pad20)") (class "Default")
      (node (ref "SV2") (pin "20") (pinfunction "20_20") (pintype "passive"))
    )
  )
)
